# LPCB234_-_BMS_INTERFACE.net
KiCad netlist of a schematic drawn in Altium Designer
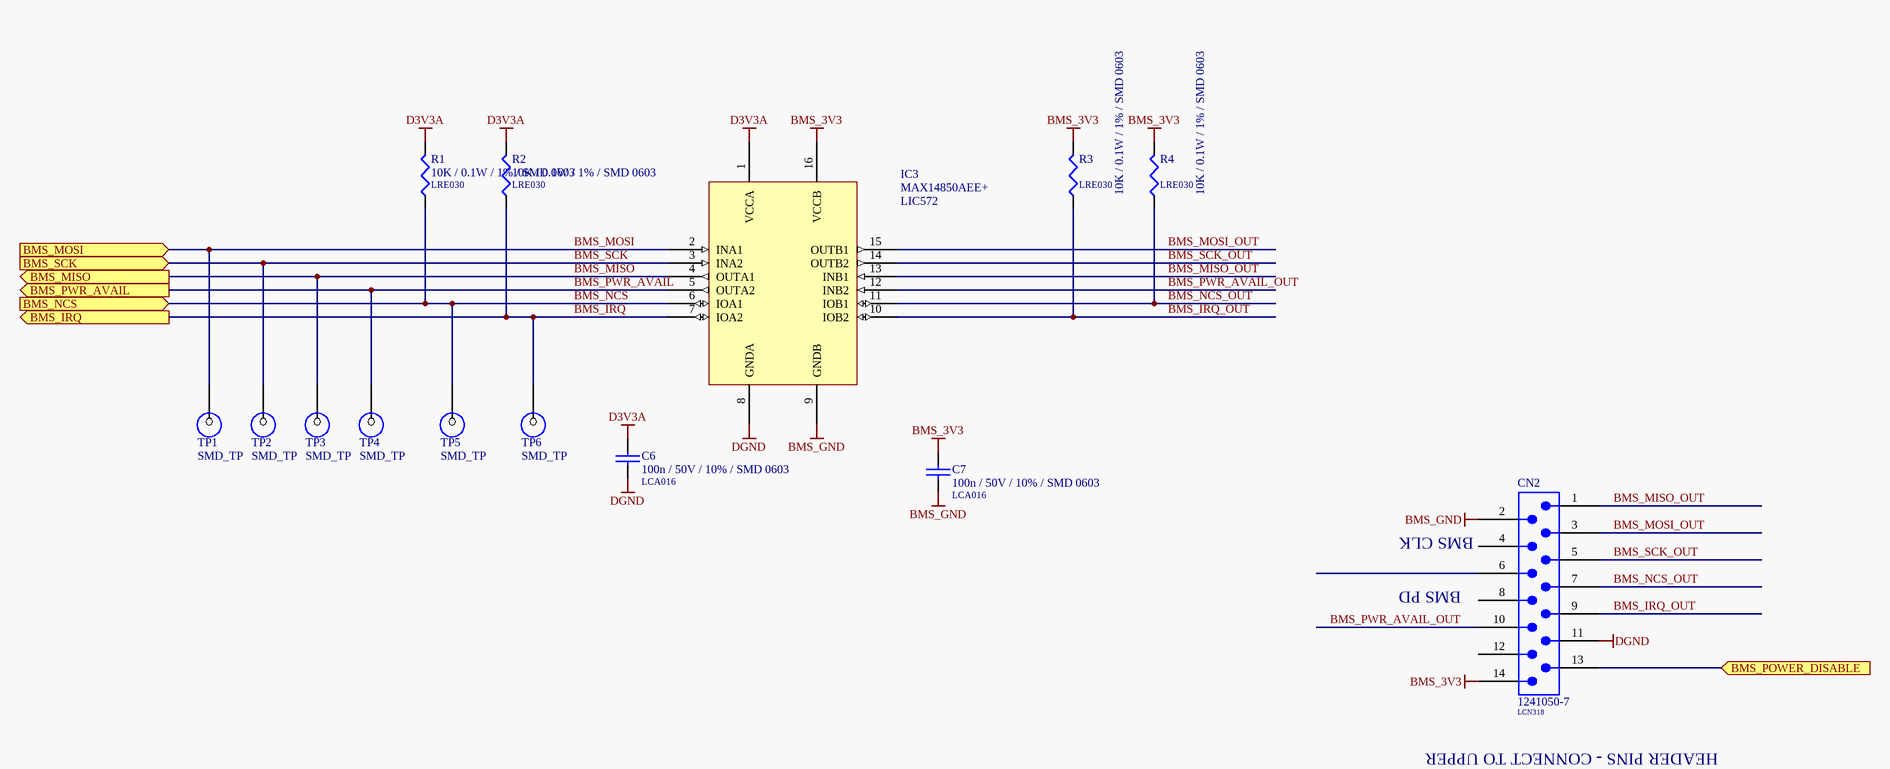
[diagram p0: LPCB234 - BMS INTERFACE.SchDoc]

(export (version "E")
  (design (tool "Eeschema 10.0.6"))
  (components
    (comp (ref "C6")
      (value "100n / 50V / 10% / SMD 0603")
      (footprint "LFP011__CC1608-0603-IPC7351_B")
      (description "Capacitor, Ceramic Chip, 100nF (0.1uF), 50V, 5%, SMD 0603 [LCA016]")
      (fields (field (name "LDL_NUMBER") "LCA016"))
      (libsource (lib "LDL_Capacitors") (part "100n / 50V / 10% / SMD 0603"))
    )
    (comp (ref "C7")
      (value "100n / 50V / 10% / SMD 0603")
      (footprint "LFP011__CC1608-0603-IPC7351_B")
      (description "Capacitor, Ceramic Chip, 100nF (0.1uF), 50V, 5%, SMD 0603 [LCA016]")
      (fields (field (name "LDL_NUMBER") "LCA016"))
      (libsource (lib "LDL_Capacitors") (part "100n / 50V / 10% / SMD 0603"))
    )
    (comp (ref "CN2")
      (value "1241050-7")
      (footprint "1241050-7")
      (description "Connector, Header, 2.54mm, 7 Pins x 2 Rows, SMD")
      (fields (field (name "LDL_NUMBER") "LCN318"))
      (libsource (lib "LDL_Connectors") (part "1241050-7"))
    )
    (comp (ref "IC3")
      (value "MAX14850AEE+")
      (footprint "LFP137__PW016")
      (description "IC, 6 Channel Digital Isolator, SMD [LIC572]")
      (fields (field (name "LDL_NUMBER") "LIC572"))
      (libsource (lib "LDL_Semiconductors") (part "MAX14850AEE+"))
    )
    (comp (ref "R1")
      (value "10K / 0.1W / 1% / SMD 0603")
      (footprint "LFP020__CR1608-0603-IPC7351_B")
      (description "Resistor, Ceramic Chip, 10K, 0.1W, 1%, SMD 0603 [LRE030]")
      (fields (field (name "LDL_NUMBER") "LRE030"))
      (libsource (lib "LDL_Resistors") (part "10K / 0.1W / 1% / SMD 0603"))
    )
    (comp (ref "R2")
      (value "10K / 0.1W / 1% / SMD 0603")
      (footprint "LFP020__CR1608-0603-IPC7351_B")
      (description "Resistor, Ceramic Chip, 10K, 0.1W, 1%, SMD 0603 [LRE030]")
      (fields (field (name "LDL_NUMBER") "LRE030"))
      (libsource (lib "LDL_Resistors") (part "10K / 0.1W / 1% / SMD 0603"))
    )
    (comp (ref "R3")
      (value "10K / 0.1W / 1% / SMD 0603")
      (footprint "LFP020__CR1608-0603-IPC7351_B")
      (description "Resistor, Ceramic Chip, 10K, 0.1W, 1%, SMD 0603 [LRE030]")
      (fields (field (name "LDL_NUMBER") "LRE030"))
      (libsource (lib "LDL_Resistors") (part "10K / 0.1W / 1% / SMD 0603"))
    )
    (comp (ref "R4")
      (value "10K / 0.1W / 1% / SMD 0603")
      (footprint "LFP020__CR1608-0603-IPC7351_B")
      (description "Resistor, Ceramic Chip, 10K, 0.1W, 1%, SMD 0603 [LRE030]")
      (fields (field (name "LDL_NUMBER") "LRE030"))
      (libsource (lib "LDL_Resistors") (part "10K / 0.1W / 1% / SMD 0603"))
    )
    (comp (ref "TP1")
      (value "SMD_TP")
      (footprint "SMD-TP")
      (description "SMD Test Point")
      (libsource (lib "LDL_Connectors") (part "SMD_TP"))
    )
    (comp (ref "TP2")
      (value "SMD_TP")
      (footprint "SMD-TP")
      (description "SMD Test Point")
      (libsource (lib "LDL_Connectors") (part "SMD_TP"))
    )
    (comp (ref "TP3")
      (value "SMD_TP")
      (footprint "SMD-TP")
      (description "SMD Test Point")
      (libsource (lib "LDL_Connectors") (part "SMD_TP"))
    )
    (comp (ref "TP4")
      (value "SMD_TP")
      (footprint "SMD-TP")
      (description "SMD Test Point")
      (libsource (lib "LDL_Connectors") (part "SMD_TP"))
    )
    (comp (ref "TP5")
      (value "SMD_TP")
      (footprint "SMD-TP")
      (description "SMD Test Point")
      (libsource (lib "LDL_Connectors") (part "SMD_TP"))
    )
    (comp (ref "TP6")
      (value "SMD_TP")
      (footprint "SMD-TP")
      (description "SMD Test Point")
      (libsource (lib "LDL_Connectors") (part "SMD_TP"))
    )
  )
  (nets
    (net (code "1") (name "/BMS_IRQ") (class "Default")
      (node (ref "IC3") (pin "7") (pinfunction "IOA2_7") (pintype "bidirectional"))
      (node (ref "R2") (pin "1") (pintype "passive"))
      (node (ref "TP6") (pin "1") (pintype "passive"))
    )
    (net (code "2") (name "/BMS_IRQ_OUT") (class "Default")
      (node (ref "CN2") (pin "9") (pinfunction "9_9") (pintype "passive"))
      (node (ref "IC3") (pin "10") (pinfunction "IOB2_10") (pintype "bidirectional"))
      (node (ref "R3") (pin "1") (pintype "passive"))
    )
    (net (code "3") (name "/BMS_MISO") (class "Default")
      (node (ref "IC3") (pin "4") (pinfunction "OUTA1_4") (pintype "output"))
      (node (ref "TP3") (pin "1") (pintype "passive"))
    )
    (net (code "4") (name "/BMS_MISO_OUT") (class "Default")
      (node (ref "CN2") (pin "1") (pinfunction "1_1") (pintype "passive"))
      (node (ref "IC3") (pin "13") (pinfunction "INB1_13") (pintype "input"))
    )
    (net (code "5") (name "/BMS_MOSI") (class "Default")
      (node (ref "IC3") (pin "2") (pinfunction "INA1_2") (pintype "input"))
      (node (ref "TP1") (pin "1") (pintype "passive"))
    )
    (net (code "6") (name "/BMS_MOSI_OUT") (class "Default")
      (node (ref "CN2") (pin "3") (pinfunction "3_3") (pintype "passive"))
      (node (ref "IC3") (pin "15") (pinfunction "OUTB1_15") (pintype "output"))
    )
    (net (code "7") (name "/BMS_NCS") (class "Default")
      (node (ref "IC3") (pin "6") (pinfunction "IOA1_6") (pintype "bidirectional"))
      (node (ref "R1") (pin "1") (pintype "passive"))
      (node (ref "TP5") (pin "1") (pintype "passive"))
    )
    (net (code "8") (name "/BMS_NCS_OUT") (class "Default")
      (node (ref "CN2") (pin "7") (pinfunction "7_7") (pintype "passive"))
      (node (ref "IC3") (pin "11") (pinfunction "IOB1_11") (pintype "bidirectional"))
      (node (ref "R4") (pin "1") (pintype "passive"))
    )
    (net (code "9") (name "/BMS_POWER_DISABLE") (class "Default")
      (node (ref "CN2") (pin "13") (pinfunction "13_13") (pintype "passive"))
    )
    (net (code "10") (name "/BMS_PWR_AVAIL") (class "Default")
      (node (ref "IC3") (pin "5") (pinfunction "OUTA2_5") (pintype "output"))
      (node (ref "TP4") (pin "1") (pintype "passive"))
    )
    (net (code "11") (name "/BMS_PWR_AVAIL_OUT") (class "Default")
      (node (ref "CN2") (pin "10") (pinfunction "10_10") (pintype "passive"))
      (node (ref "IC3") (pin "12") (pinfunction "INB2_12") (pintype "input"))
    )
    (net (code "12") (name "/BMS_SCK") (class "Default")
      (node (ref "IC3") (pin "3") (pinfunction "INA2_3") (pintype "input"))
      (node (ref "TP2") (pin "1") (pintype "passive"))
    )
    (net (code "13") (name "/BMS_SCK_OUT") (class "Default")
      (node (ref "CN2") (pin "5") (pinfunction "5_5") (pintype "passive"))
      (node (ref "IC3") (pin "14") (pinfunction "OUTB2_14") (pintype "output"))
    )
    (net (code "14") (name "BMS_3V3") (class "Default")
      (node (ref "C7") (pin "1") (pintype "passive"))
      (node (ref "CN2") (pin "14") (pinfunction "14_14") (pintype "passive"))
      (node (ref "IC3") (pin "16") (pinfunction "VCCB_16") (pintype "power_in"))
      (node (ref "R3") (pin "2") (pintype "passive"))
      (node (ref "R4") (pin "2") (pintype "passive"))
    )
    (net (code "15") (name "BMS_GND") (class "Default")
      (node (ref "C7") (pin "2") (pintype "passive"))
      (node (ref "CN2") (pin "2") (pinfunction "2_2") (pintype "passive"))
      (node (ref "IC3") (pin "9") (pinfunction "GNDB_9") (pintype "power_in"))
    )
    (net (code "16") (name "D3V3A") (class "Default")
      (node (ref "C6") (pin "1") (pintype "passive"))
      (node (ref "IC3") (pin "1") (pinfunction "VCCA_1") (pintype "power_in"))
      (node (ref "R1") (pin "2") (pintype "passive"))
      (node (ref "R2") (pin "2") (pintype "passive"))
    )
    (net (code "17") (name "DGND") (class "Default")
      (node (ref "C6") (pin "2") (pintype "passive"))
      (node (ref "CN2") (pin "11") (pinfunction "11_11") (pintype "passive"))
      (node (ref "IC3") (pin "8") (pinfunction "GNDA_8") (pintype "power_in"))
    )
    (net (code "18") (name "unconnected-(CN2-Pad4)") (class "Default")
      (node (ref "CN2") (pin "4") (pinfunction "4_4") (pintype "passive"))
    )
    (net (code "19") (name "unconnected-(CN2-Pad6)") (class "Default")
      (node (ref "CN2") (pin "6") (pinfunction "6_6") (pintype "passive"))
    )
    (net (code "20") (name "unconnected-(CN2-Pad8)") (class "Default")
      (node (ref "CN2") (pin "8") (pinfunction "8_8") (pintype "passive"))
    )
    (net (code "21") (name "unconnected-(CN2-Pad12)") (class "Default")
      (node (ref "CN2") (pin "12") (pinfunction "12_12") (pintype "passive"))
    )
  )
)
